# Power_Converter_Circuit.net
KiCad netlist of a schematic drawn in Altium Designer
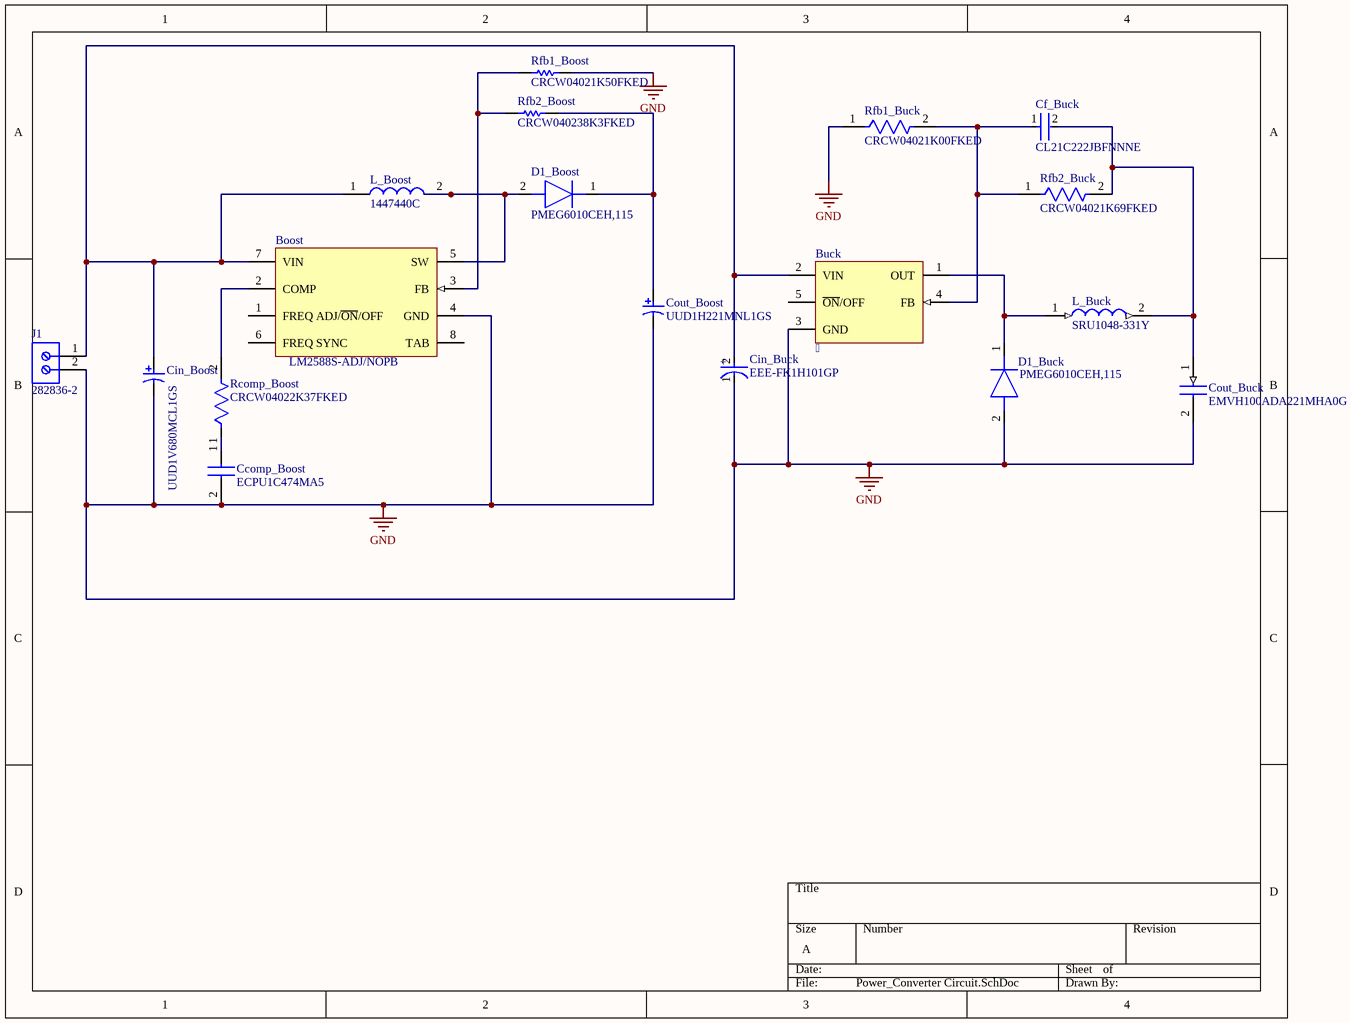
[diagram p0: Power_Converter Circuit.SchDoc]

(export (version "E")
  (design (tool "Eeschema 10.0.6"))
  (components
    (comp (ref "Boost")
      (value "LM2588S-ADJ/NOPB")
      (footprint "KTW0007B_N")
      (description "SIMPLE SWITCHER® 5A Flyback Regulator with Shutdown, 7-pin TO-263, Pb-Free")
      (fields (field (name "MANUFACTURER") "Texas Instruments"))
      (libsource (lib "Altium Content Vault") (part "PM-SWREG-LM2586S-12"))
    )
    (comp (ref "Buck")
      (value "")
      (footprint "NDH0005A")
      (description "SIMPLE SWITCHER® Power Converter 150 KHz 1A Step-Down Voltage Regulator, 5-pin TO-220, Pb-Free")
      (fields (field (name "MANUFACTURER") "Texas Instruments"))
      (libsource (lib "Altium Content Vault") (part "PM-REG-LM2595T-12"))
    )
    (comp (ref "Ccomp_Boost")
      (value "ECPU1C474MA5")
      (footprint "SamacSys:ECPU1C154MA5")
      (description "Capacitor")
      (libsource (lib "*") (part "ECPU1C474MA5"))
    )
    (comp (ref "Cf_Buck")
      (value "CL21C222JBFNNNE")
      (footprint "FP-CL21-IPC_C")
      (description "CL21 Series 0805 2.2nF 50V ±5% Tolerance C0G Multilayer Ceramic Chip Capacitor")
      (fields (field (name "TOLERANCE") "5%") (field (name "VOLTAGE") "50V"))
      (libsource (lib "Altium Content Vault") (part "b4654b650e69147ec39a6b967a45e02"))
    )
    (comp (ref "Cin_Boost")
      (value "UUD1V680MCL1GS")
      (footprint "NIC-CAPA2-6.3X7.7_V")
      (fields (field (name "MANUFACTURER") "Nichicon"))
      (libsource (lib "Altium Content Vault") (part "NIC-CAP-P-2"))
    )
    (comp (ref "Cin_Buck")
      (value "EEE-FK1H101GP")
      (footprint "FP-FKF-MFG")
      (description "CAP ALUM 100UF 20% 50V SMD")
      (fields (field (name "VOLTAGE") "50V") (field (name "TOLERANCE") "20%"))
      (libsource (lib "Altium Content Vault") (part "203bc49f2ac43e59fd269a8c329ed05"))
    )
    (comp (ref "Cout_Boost")
      (value "UUD1H221MNL1GS")
      (footprint "NIC-CAPA2-10X10_V")
      (fields (field (name "MANUFACTURER") "Nichicon"))
      (libsource (lib "Altium Content Vault") (part "NIC-CAP-P-2"))
    )
    (comp (ref "Cout_Buck")
      (value "EMVH100ADA221MHA0G")
      (footprint "SamacSys:CAPAE830X1050N")
      (description "Capacitor")
      (libsource (lib "*") (part "EMVH100ADA221MHA0G"))
    )
    (comp (ref "D1_Boost")
      (value "PMEG6010CEH,115")
      (footprint "SamacSys:SODFL3516X120N")
      (description "Diode")
      (fields (field (name "MOUSER PART NUMBER") "771-PMEG6010CEH-T/R"))
      (libsource (lib "*") (part "PMEG6010CEH,115"))
    )
    (comp (ref "D1_Buck")
      (value "PMEG6010CEH,115")
      (footprint "SamacSys:SODFL3516X120N")
      (description "Diode")
      (fields (field (name "MOUSER PART NUMBER") "771-PMEG6010CEH-T/R"))
      (libsource (lib "*") (part "PMEG6010CEH,115"))
    )
    (comp (ref "J1")
      (value "282836-2")
      (footprint "TECO-282836-2_V")
      (description "Female Header, Pitch 5 mm, 1 x 2 Position, Height 10 mm, Tail Length 3.5 mm, Rohs, Bulk")
      (fields (field (name "VOLTAGE") "300V") (field (name "MANUFACTURER") "TE Connectivity"))
      (libsource (lib "Altium Content Vault") (part "CN-1P-F-TB2"))
    )
    (comp (ref "L_Boost")
      (value "1447440C")
      (footprint "SamacSys:1447440C")
      (description "Inductor")
      (fields (field (name "MOUSER PART NUMBER") "580-1447440C"))
      (libsource (lib "*") (part "1447440C"))
    )
    (comp (ref "L_Buck")
      (value "SRU1048-331Y")
      (footprint "SamacSys:INDPM100100X510N")
      (description "Inductor")
      (libsource (lib "*") (part "SRU1048-331Y"))
    )
    (comp (ref "Rcomp_Boost")
      (value "CRCW04022K37FKED")
      (footprint "FP-CRCW0402-e3-IPC_B")
      (description "RES Thick Film, 2.37kΩ, 1%, 0.063W, 100ppm/°C, 0402")
      (fields (field (name "TOLERANCE") "1%"))
      (libsource (lib "Altium Content Vault") (part "1029c3af85768c4190bb7ad29bc67b5"))
    )
    (comp (ref "Rfb1_Boost")
      (value "CRCW04021K50FKED")
      (footprint "RESC1005X40X25NL05T05")
      (fields (field (name "MANUFACTURER") "Vishay Dale"))
      (libsource (lib "Altium Content Vault") (part "RES"))
    )
    (comp (ref "Rfb1_Buck")
      (value "CRCW04021K00FKED")
      (footprint "FP-CRCW0402-e3-MFG")
      (description "RES Thick Film, 1kΩ, 1%, 0.063W, 100ppm/°C, 0402")
      (fields (field (name "TOLERANCE") "1%"))
      (libsource (lib "Altium Content Vault") (part "1029c3af85768c4190bb7ad29bc67b5"))
    )
    (comp (ref "Rfb2_Boost")
      (value "CRCW040238K3FKED")
      (footprint "RESC1005X40X25NL05T05")
      (fields (field (name "MANUFACTURER") "Vishay Dale"))
      (libsource (lib "Altium Content Vault") (part "RES"))
    )
    (comp (ref "Rfb2_Buck")
      (value "CRCW04021K69FKED")
      (footprint "FP-CRCW0402-e3-IPC_A")
      (description "RES Thick Film, 1.69kΩ, 1%, 0.063W, 100ppm/°C, 0402")
      (fields (field (name "TOLERANCE") "1%"))
      (libsource (lib "Altium Content Vault") (part "1029c3af85768c4190bb7ad29bc67b5"))
    )
  )
  (nets
    (net (code "1") (name "GND") (class "Default")
      (node (ref "Boost") (pin "4") (pinfunction "GND_4") (pintype "power_in"))
      (node (ref "Buck") (pin "3") (pinfunction "GND_3") (pintype "power_in"))
      (node (ref "Ccomp_Boost") (pin "2") (pinfunction "2_2") (pintype "passive"))
      (node (ref "Cin_Boost") (pin "2") (pinfunction "2_2") (pintype "passive"))
      (node (ref "Cin_Buck") (pin "1") (pinfunction "C_1") (pintype "passive"))
      (node (ref "Cout_Boost") (pin "2") (pinfunction "2_2") (pintype "passive"))
      (node (ref "Cout_Buck") (pin "2") (pinfunction "-_2") (pintype "passive"))
      (node (ref "D1_Buck") (pin "2") (pinfunction "A_2") (pintype "passive"))
      (node (ref "J1") (pin "2") (pinfunction "2_2") (pintype "passive"))
      (node (ref "Rfb1_Boost") (pin "2") (pinfunction "2_2") (pintype "passive"))
      (node (ref "Rfb1_Buck") (pin "1") (pinfunction "1_1") (pintype "passive"))
    )
    (net (code "2") (name "Net-(Boost-COMP)") (class "Default")
      (node (ref "Boost") (pin "2") (pinfunction "COMP_2") (pintype "passive"))
      (node (ref "Rcomp_Boost") (pin "2") (pinfunction "2_2") (pintype "passive"))
    )
    (net (code "3") (name "Net-(Boost-FB)") (class "Default")
      (node (ref "Boost") (pin "3") (pinfunction "FB_3") (pintype "input"))
      (node (ref "Rfb1_Boost") (pin "1") (pinfunction "1_1") (pintype "passive"))
      (node (ref "Rfb2_Boost") (pin "1") (pinfunction "1_1") (pintype "passive"))
    )
    (net (code "4") (name "Net-(Boost-SW)") (class "Default")
      (node (ref "Boost") (pin "5") (pinfunction "SW_5") (pintype "power_in"))
      (node (ref "D1_Boost") (pin "2") (pinfunction "A_2") (pintype "passive"))
      (node (ref "L_Boost") (pin "2") (pinfunction "2_2") (pintype "passive"))
    )
    (net (code "5") (name "Net-(Boost-VIN)") (class "Default")
      (node (ref "Boost") (pin "7") (pinfunction "VIN_7") (pintype "power_in"))
      (node (ref "Buck") (pin "2") (pinfunction "VIN_2") (pintype "power_in"))
      (node (ref "Cin_Boost") (pin "1") (pinfunction "1_1") (pintype "passive"))
      (node (ref "Cin_Buck") (pin "2") (pinfunction "A_2") (pintype "passive"))
      (node (ref "J1") (pin "1") (pinfunction "1_1") (pintype "passive"))
      (node (ref "L_Boost") (pin "1") (pinfunction "1_1") (pintype "passive"))
    )
    (net (code "6") (name "Net-(Buck-FB)") (class "Default")
      (node (ref "Buck") (pin "4") (pinfunction "FB_4") (pintype "input"))
      (node (ref "Cf_Buck") (pin "1") (pinfunction "1_1") (pintype "passive"))
      (node (ref "Rfb1_Buck") (pin "2") (pinfunction "2_2") (pintype "passive"))
      (node (ref "Rfb2_Buck") (pin "1") (pinfunction "1_1") (pintype "passive"))
    )
    (net (code "7") (name "Net-(Buck-OUT)") (class "Default")
      (node (ref "Buck") (pin "1") (pinfunction "OUT_1") (pintype "power_in"))
      (node (ref "D1_Buck") (pin "1") (pinfunction "K_1") (pintype "passive"))
      (node (ref "L_Buck") (pin "1") (pinfunction "1_1") (pintype "input"))
    )
    (net (code "8") (name "Net-(Ccomp_Boost-Pad1)") (class "Default")
      (node (ref "Ccomp_Boost") (pin "1") (pinfunction "1_1") (pintype "passive"))
      (node (ref "Rcomp_Boost") (pin "1") (pinfunction "1_1") (pintype "passive"))
    )
    (net (code "9") (name "Net-(Cout_Buck-+)") (class "Default")
      (node (ref "Cf_Buck") (pin "2") (pinfunction "2_2") (pintype "passive"))
      (node (ref "Cout_Buck") (pin "1") (pinfunction "+_1") (pintype "input"))
      (node (ref "L_Buck") (pin "2") (pinfunction "2_2") (pintype "output"))
      (node (ref "Rfb2_Buck") (pin "2") (pinfunction "2_2") (pintype "passive"))
    )
    (net (code "10") (name "Net-(D1_Boost-K)") (class "Default")
      (node (ref "Cout_Boost") (pin "1") (pinfunction "1_1") (pintype "passive"))
      (node (ref "D1_Boost") (pin "1") (pinfunction "K_1") (pintype "passive"))
      (node (ref "Rfb2_Boost") (pin "2") (pinfunction "2_2") (pintype "passive"))
    )
    (net (code "11") (name "unconnected-(Boost-FREQ_ADJ{slash}~{ON}{slash}OFF-Pad1)") (class "Default")
      (node (ref "Boost") (pin "1") (pinfunction "FREQ_ADJ/~{ON}/OFF_1") (pintype "passive"))
    )
    (net (code "12") (name "unconnected-(Boost-FREQ_SYNC-Pad6)") (class "Default")
      (node (ref "Boost") (pin "6") (pinfunction "FREQ_SYNC_6") (pintype "passive"))
    )
    (net (code "13") (name "unconnected-(Boost-TAB-Pad8)") (class "Default")
      (node (ref "Boost") (pin "8") (pinfunction "TAB_8") (pintype "passive"))
    )
    (net (code "14") (name "unconnected-(Buck-~{ON}{slash}OFF-Pad5)") (class "Default")
      (node (ref "Buck") (pin "5") (pinfunction "~{ON}/OFF_5") (pintype "passive"))
    )
  )
)
